# magnet-motor-encoder_v1.net
KiCad netlist of a schematic drawn in EAGLE
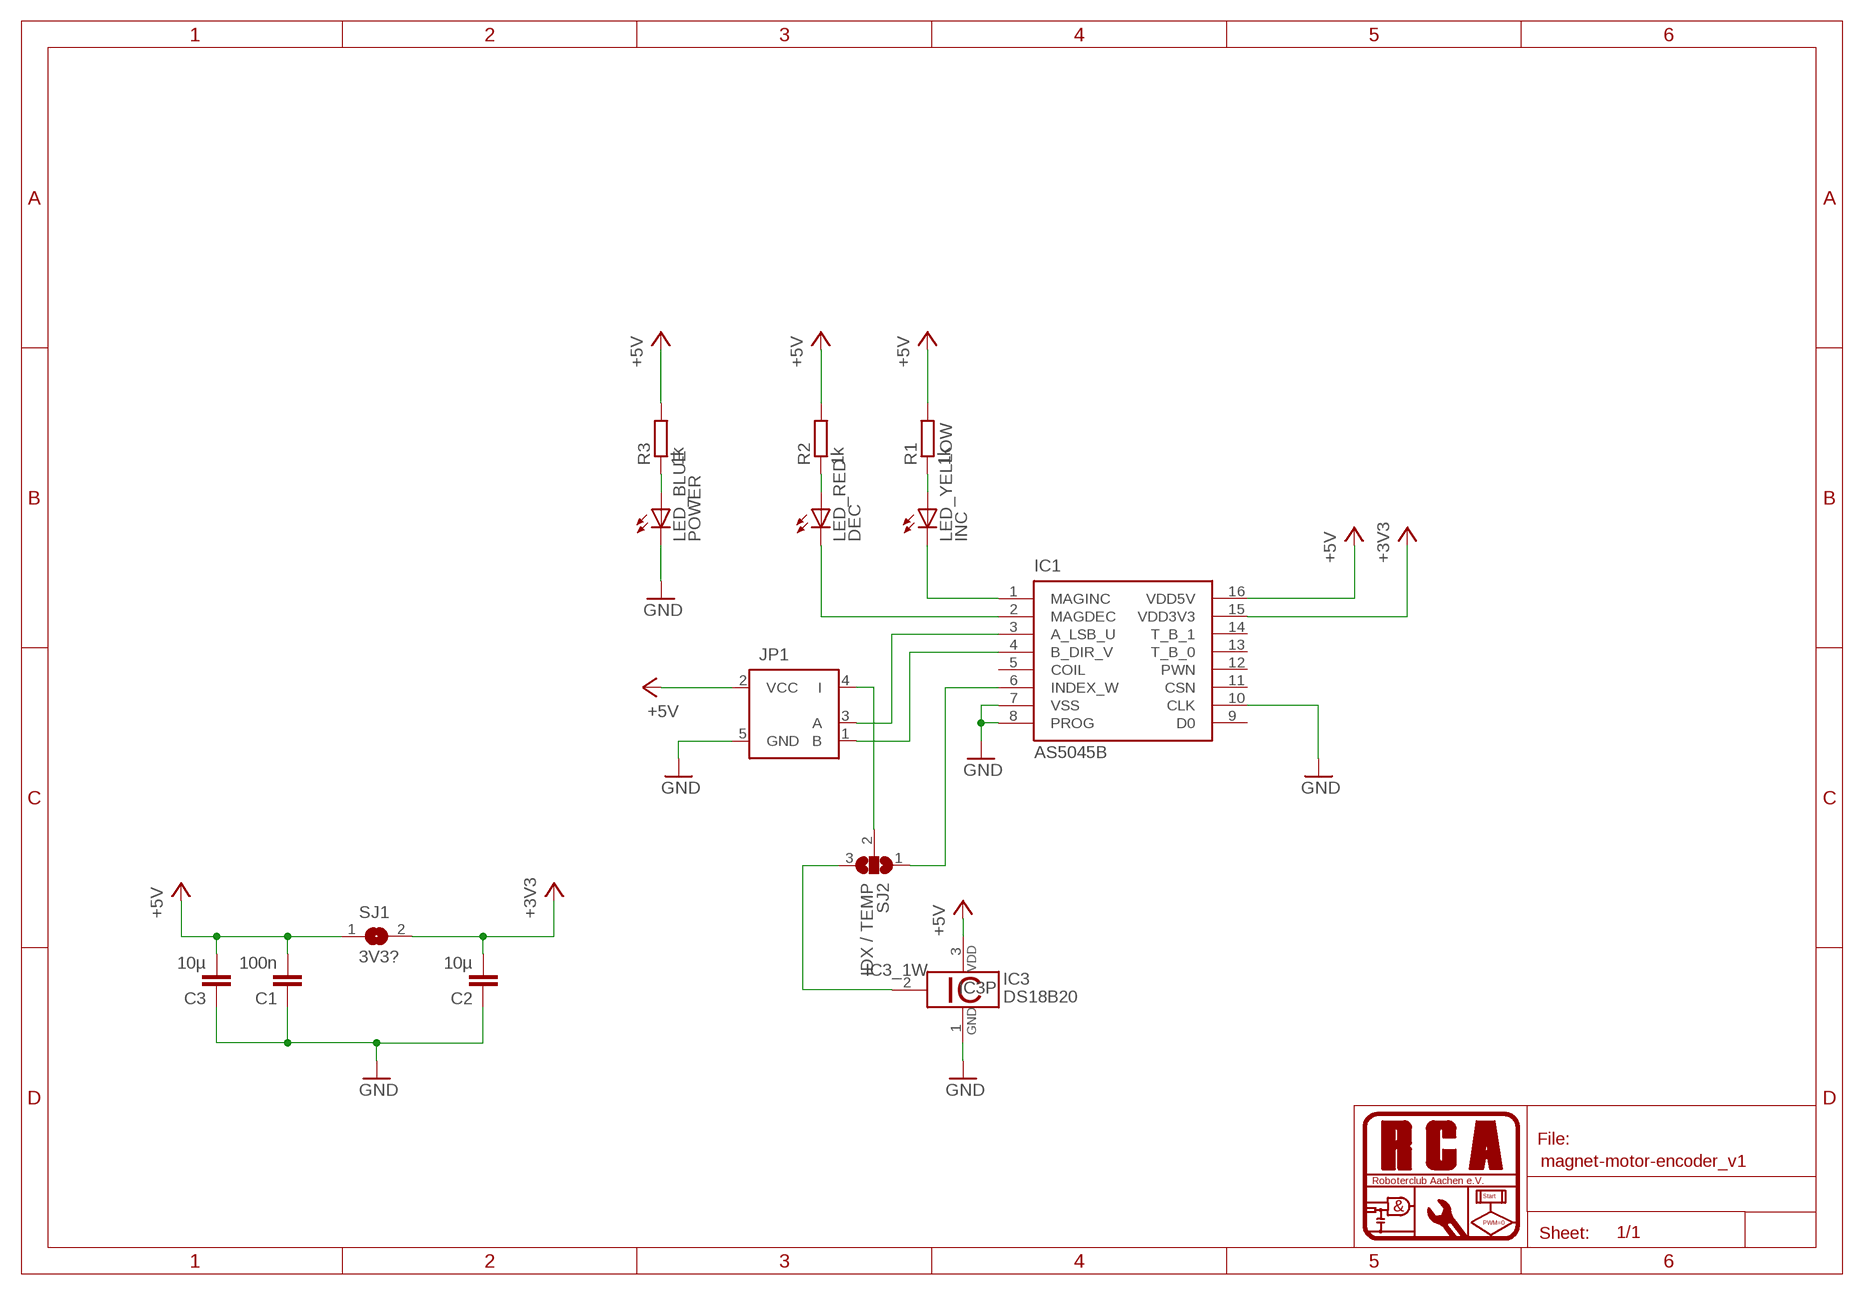
[diagram p0: schematic, sheet 1]

(export (version "E")
  (design (tool "Eeschema 10.0.6"))
  (components
    (comp (ref "C1")
      (value "100n")
      (footprint "eagle-import:C0805K")
      (libsource (lib "eagle-import") (part "C-EUC0805K"))
    )
    (comp (ref "C2")
      (value "10µ")
      (footprint "eagle-import:C0805K")
      (libsource (lib "eagle-import") (part "C-EUC0805K"))
    )
    (comp (ref "C3")
      (value "10µ")
      (footprint "eagle-import:C0805K")
      (libsource (lib "eagle-import") (part "C-EUC0805K"))
    )
    (comp (ref "IC1")
      (value "AS5045B")
      (footprint "eagle-import:SSOP16")
      (fields (field (name "MPN") "AS5040ASSU"))
      (libsource (lib "eagle-import") (part "AS5040"))
    )
    (comp (ref "IC3")
      (value "DS18B20")
      (footprint "eagle-import:TO92-")
      (libsource (lib "eagle-import") (part "DS18S20"))
    )
    (comp (ref "JP1")
      (value "ENCODERPSS")
      (footprint "eagle-import:22-23-2051")
      (libsource (lib "eagle-import") (part "ENCODERPSS"))
    )
    (comp (ref "LED_BLUE")
      (value "POWER")
      (footprint "eagle-import:CHIPLED_0805")
      (libsource (lib "eagle-import") (part "LEDCHIPLED_0805"))
    )
    (comp (ref "LED_RED")
      (value "DEC")
      (footprint "eagle-import:CHIPLED_0805")
      (libsource (lib "eagle-import") (part "LEDCHIPLED_0805"))
    )
    (comp (ref "LED_YELLOW")
      (value "INC")
      (footprint "eagle-import:CHIPLED_0805")
      (libsource (lib "eagle-import") (part "LEDCHIPLED_0805"))
    )
    (comp (ref "R1")
      (value "1k")
      (footprint "eagle-import:R0805")
      (libsource (lib "eagle-import") (part "R-EU_R0805"))
    )
    (comp (ref "R2")
      (value "1k")
      (footprint "eagle-import:R0805")
      (libsource (lib "eagle-import") (part "R-EU_R0805"))
    )
    (comp (ref "R3")
      (value "1k")
      (footprint "eagle-import:R0805")
      (libsource (lib "eagle-import") (part "R-EU_R0805"))
    )
    (comp (ref "SJ1")
      (value "3V3?")
      (footprint "eagle-import:SJS")
      (libsource (lib "eagle-import") (part "SJS"))
    )
    (comp (ref "SJ2")
      (value "IDX / TEMP")
      (footprint "eagle-import:SJ_2")
      (libsource (lib "eagle-import") (part "SJ2W"))
    )
  )
  (nets
    (net (code "1") (name "+3V3") (class "Default")
      (node (ref "C2") (pin "2") (pinfunction "2_2") (pintype "passive"))
      (node (ref "IC1") (pin "15") (pinfunction "VDD3V3_15") (pintype "passive"))
      (node (ref "SJ1") (pin "2") (pinfunction "2_2") (pintype "passive"))
    )
    (net (code "2") (name "+5V") (class "Default")
      (node (ref "C1") (pin "2") (pinfunction "2_2") (pintype "passive"))
      (node (ref "C3") (pin "2") (pinfunction "2_2") (pintype "passive"))
      (node (ref "IC1") (pin "16") (pinfunction "VDD5V_16") (pintype "passive"))
      (node (ref "IC3") (pin "3") (pinfunction "VDD_3") (pintype "power_in"))
      (node (ref "JP1") (pin "2") (pinfunction "VCC_2") (pintype "power_in"))
      (node (ref "R1") (pin "2") (pinfunction "2_2") (pintype "passive"))
      (node (ref "R2") (pin "2") (pinfunction "2_2") (pintype "passive"))
      (node (ref "R3") (pin "2") (pinfunction "2_2") (pintype "passive"))
      (node (ref "SJ1") (pin "1") (pinfunction "1_1") (pintype "passive"))
    )
    (net (code "3") (name "GND") (class "Default")
      (node (ref "C1") (pin "1") (pinfunction "1_1") (pintype "passive"))
      (node (ref "C2") (pin "1") (pinfunction "1_1") (pintype "passive"))
      (node (ref "C3") (pin "1") (pinfunction "1_1") (pintype "passive"))
      (node (ref "IC1") (pin "10") (pinfunction "CLK_10") (pintype "input"))
      (node (ref "IC1") (pin "7") (pinfunction "VSS_7") (pintype "passive"))
      (node (ref "IC1") (pin "8") (pinfunction "PROG_8") (pintype "input"))
      (node (ref "IC3") (pin "1") (pinfunction "GND_1") (pintype "power_in"))
      (node (ref "JP1") (pin "5") (pinfunction "GND_5") (pintype "power_in"))
      (node (ref "LED_BLUE") (pin "C") (pinfunction "C_C") (pintype "passive"))
    )
    (net (code "4") (name "Net-(IC1-A_LSB_U)") (class "Default")
      (node (ref "IC1") (pin "3") (pinfunction "A_LSB_U_3") (pintype "output"))
      (node (ref "JP1") (pin "3") (pinfunction "A_3") (pintype "output"))
    )
    (net (code "5") (name "Net-(IC1-B_DIR_V)") (class "Default")
      (node (ref "IC1") (pin "4") (pinfunction "B_DIR_V_4") (pintype "output"))
      (node (ref "JP1") (pin "1") (pinfunction "B_1") (pintype "output"))
    )
    (net (code "6") (name "Net-(IC1-INDEX_W)") (class "Default")
      (node (ref "IC1") (pin "6") (pinfunction "INDEX_W_6") (pintype "output"))
      (node (ref "SJ2") (pin "1") (pinfunction "1_1") (pintype "passive"))
    )
    (net (code "7") (name "Net-(IC1-MAGDEC)") (class "Default")
      (node (ref "IC1") (pin "2") (pinfunction "MAGDEC_2") (pintype "tri_state"))
      (node (ref "LED_RED") (pin "C") (pinfunction "C_C") (pintype "passive"))
    )
    (net (code "8") (name "Net-(IC1-MAGINC)") (class "Default")
      (node (ref "IC1") (pin "1") (pinfunction "MAGINC_1") (pintype "tri_state"))
      (node (ref "LED_YELLOW") (pin "C") (pinfunction "C_C") (pintype "passive"))
    )
    (net (code "9") (name "Net-(IC3C-1W)") (class "Default")
      (node (ref "IC3") (pin "2") (pinfunction "1W_2") (pintype "power_in"))
      (node (ref "SJ2") (pin "3") (pinfunction "3_3") (pintype "passive"))
    )
    (net (code "10") (name "Net-(JP1-I)") (class "Default")
      (node (ref "JP1") (pin "4") (pinfunction "I_4") (pintype "output"))
      (node (ref "SJ2") (pin "2") (pinfunction "2_2") (pintype "passive"))
    )
    (net (code "11") (name "Net-(LED_BLUE-PadA)") (class "Default")
      (node (ref "LED_BLUE") (pin "A") (pinfunction "A_A") (pintype "passive"))
      (node (ref "R3") (pin "1") (pinfunction "1_1") (pintype "passive"))
    )
    (net (code "12") (name "Net-(LED_RED-PadA)") (class "Default")
      (node (ref "LED_RED") (pin "A") (pinfunction "A_A") (pintype "passive"))
      (node (ref "R2") (pin "1") (pinfunction "1_1") (pintype "passive"))
    )
    (net (code "13") (name "Net-(LED_YELLOW-PadA)") (class "Default")
      (node (ref "LED_YELLOW") (pin "A") (pinfunction "A_A") (pintype "passive"))
      (node (ref "R1") (pin "1") (pinfunction "1_1") (pintype "passive"))
    )
    (net (code "14") (name "unconnected-(IC1-COIL-Pad5)") (class "Default")
      (node (ref "IC1") (pin "5") (pinfunction "COIL_5") (pintype "no_connect"))
    )
    (net (code "15") (name "unconnected-(IC1-CSN-Pad11)") (class "Default")
      (node (ref "IC1") (pin "11") (pinfunction "CSN_11") (pintype "input"))
    )
    (net (code "16") (name "unconnected-(IC1-D0-Pad9)") (class "Default")
      (node (ref "IC1") (pin "9") (pinfunction "D0_9") (pintype "tri_state"))
    )
    (net (code "17") (name "unconnected-(IC1-PWN-Pad12)") (class "Default")
      (node (ref "IC1") (pin "12") (pinfunction "PWN_12") (pintype "passive"))
    )
    (net (code "18") (name "unconnected-(IC1-T_B_0-Pad13)") (class "Default")
      (node (ref "IC1") (pin "13") (pinfunction "T_B_0_13") (pintype "no_connect"))
    )
    (net (code "19") (name "unconnected-(IC1-T_B_1-Pad14)") (class "Default")
      (node (ref "IC1") (pin "14") (pinfunction "T_B_1_14") (pintype "no_connect"))
    )
  )
)
